# Server_CPU_Sub_Power_Supplies.net
KiCad netlist of a schematic drawn in Altium Designer
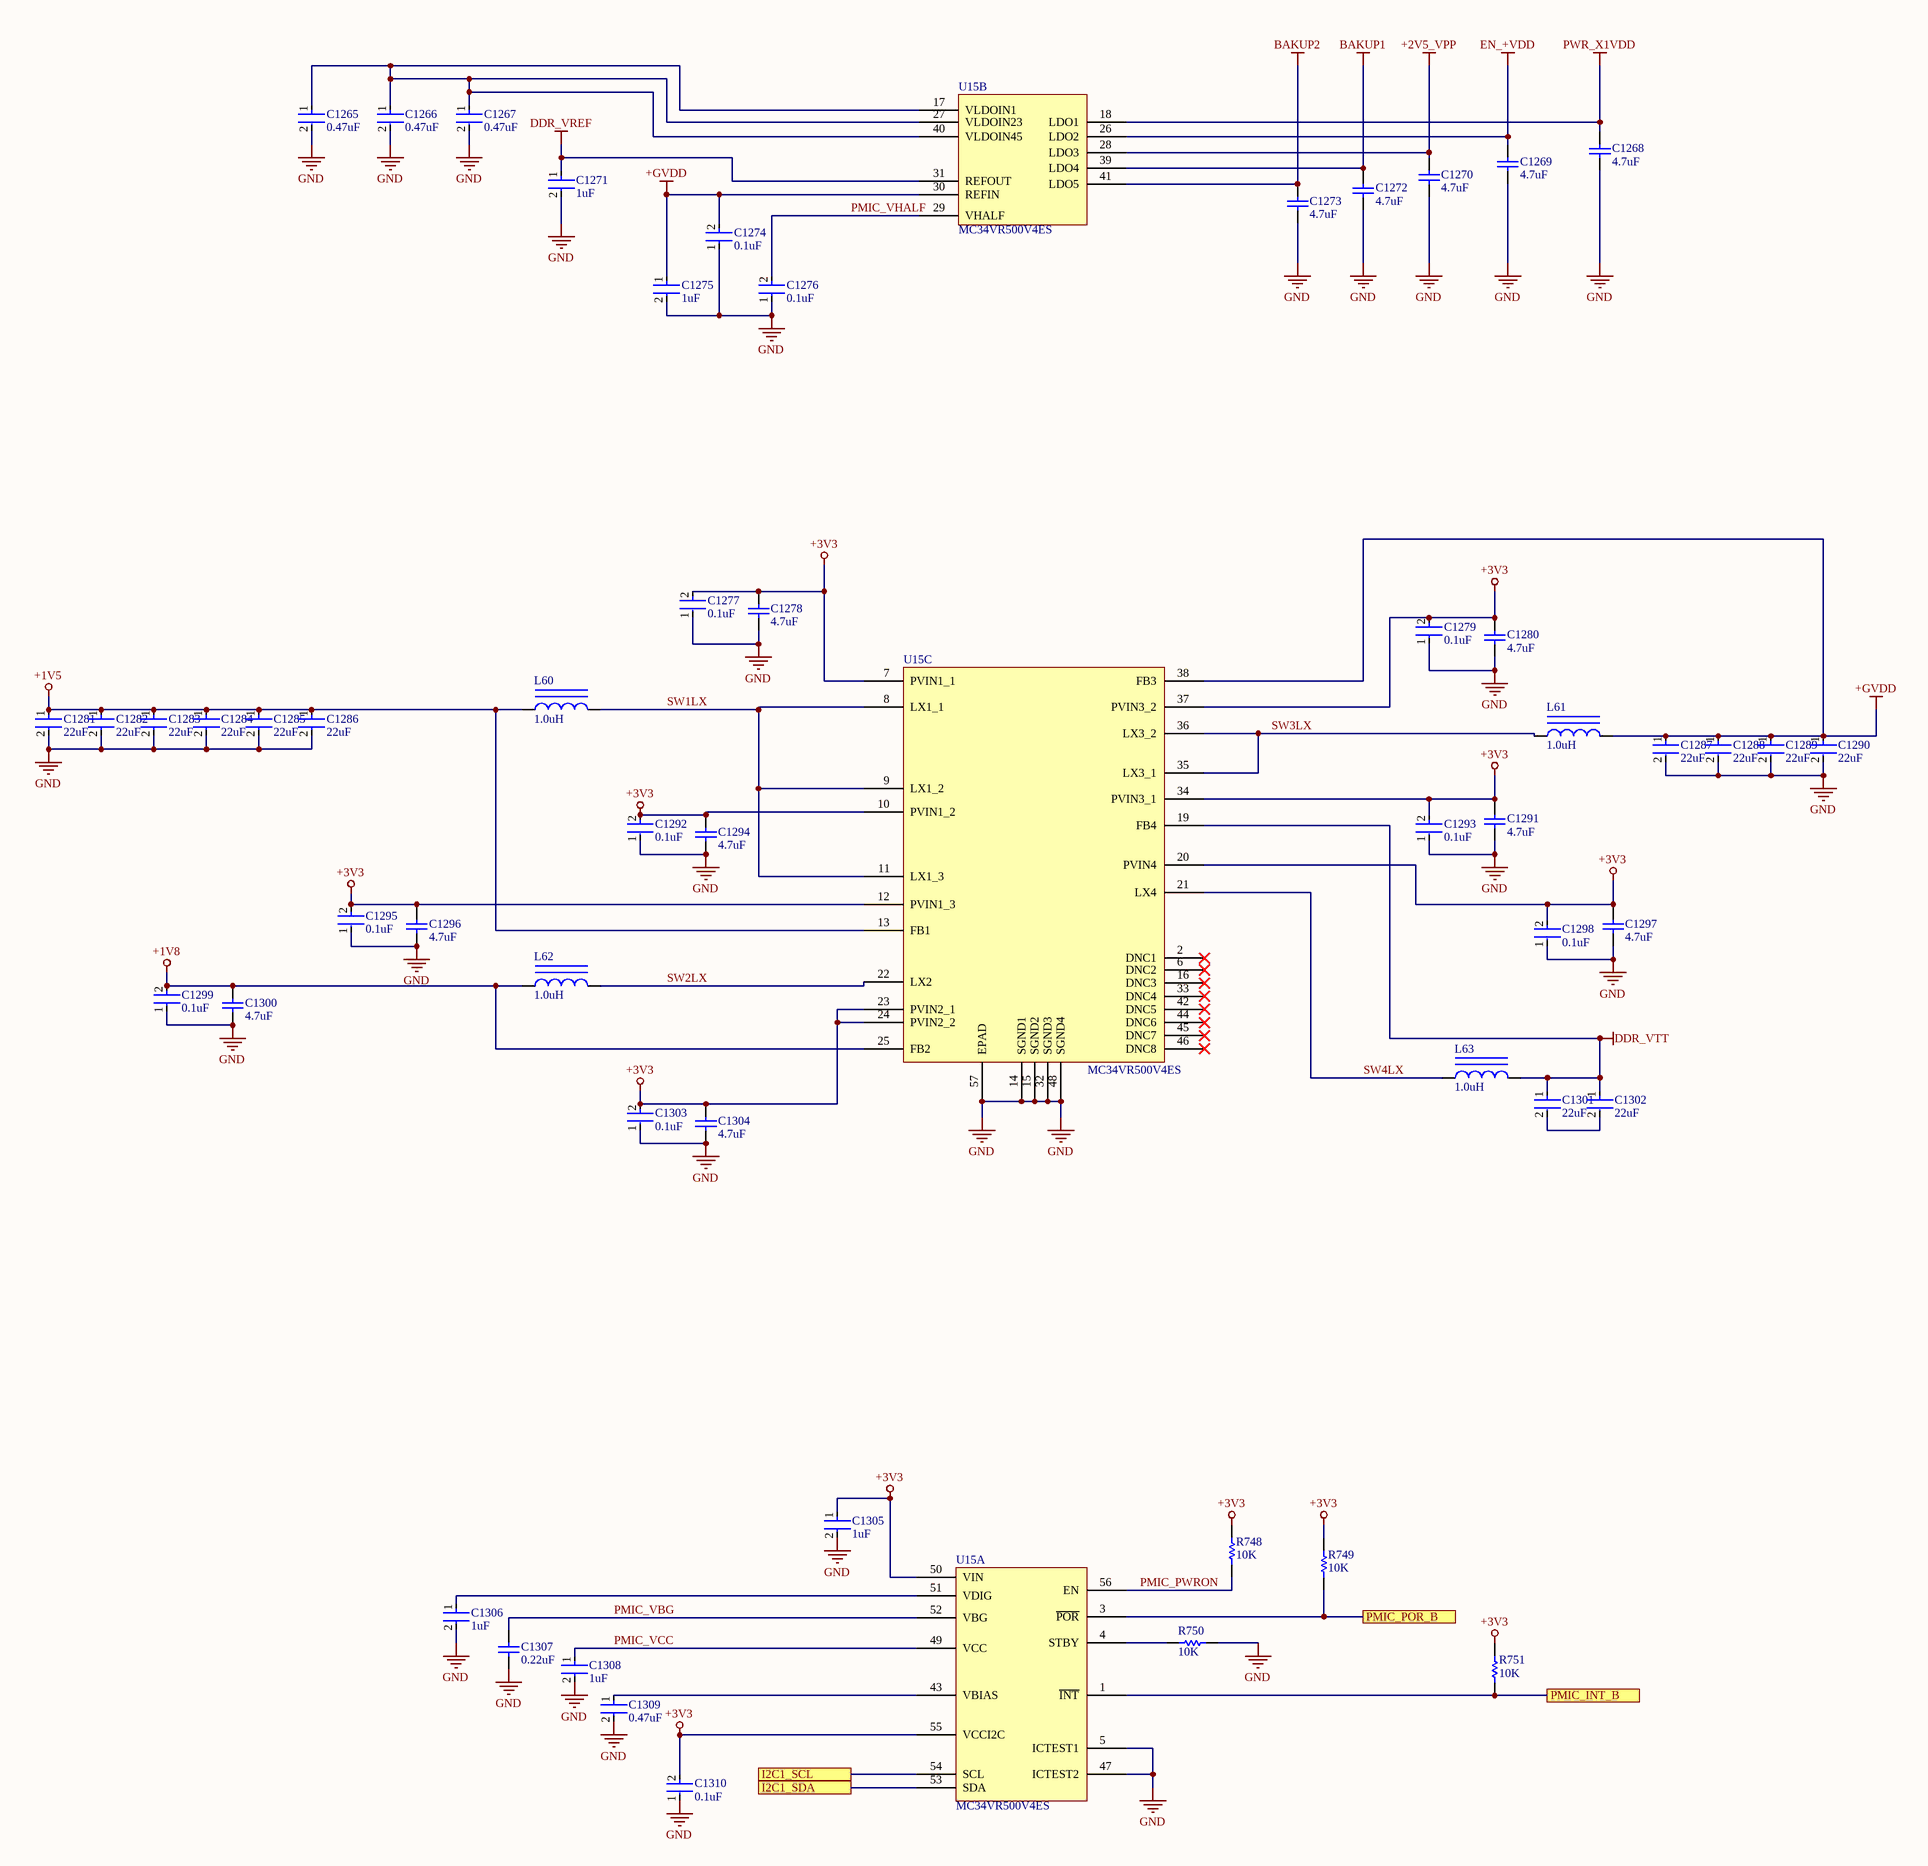
[diagram p0: Server_CPU_Sub_Power_Supplies.SchDoc]

(export (version "E")
  (design (tool "Eeschema 10.0.6"))
  (components
    (comp (ref "C1265")
      (value "0.47uF")
      (footprint "FP-GRM188-0_1-e0_2_0_5-IPC_B")
      (description "Chip Multilayer Ceramic Capacitors for General Purpose, 0603, 0.47uF, X7R, 15%, 10%, 16V")
      (fields (field (name "VOLTAGE") "16V") (field (name "TOLERANCE") "10%"))
      (libsource (lib "Altium Content Vault") (part "11868f565c42a9108669ba33697ecf6"))
    )
    (comp (ref "C1266")
      (value "0.47uF")
      (footprint "FP-GRM188-0_1-e0_2_0_5-IPC_B")
      (description "Chip Multilayer Ceramic Capacitors for General Purpose, 0603, 0.47uF, X7R, 15%, 10%, 16V")
      (fields (field (name "VOLTAGE") "16V") (field (name "TOLERANCE") "10%"))
      (libsource (lib "Altium Content Vault") (part "11868f565c42a9108669ba33697ecf6"))
    )
    (comp (ref "C1267")
      (value "0.47uF")
      (footprint "FP-GRM188-0_1-e0_2_0_5-IPC_B")
      (description "Chip Multilayer Ceramic Capacitors for General Purpose, 0603, 0.47uF, X7R, 15%, 10%, 16V")
      (fields (field (name "VOLTAGE") "16V") (field (name "TOLERANCE") "10%"))
      (libsource (lib "Altium Content Vault") (part "11868f565c42a9108669ba33697ecf6"))
    )
    (comp (ref "C1268")
      (value "4.7uF")
      (footprint "CAPC2013X145X50ML20T25")
      (fields (field (name "MANUFACTURER") "Kemet") (field (name "PART NUMBER") "C0805C475K3PACTU"))
      (libsource (lib "Altium Content Vault") (part "CAP"))
    )
    (comp (ref "C1269")
      (value "4.7uF")
      (footprint "CAPC2013X145X50ML20T25")
      (fields (field (name "MANUFACTURER") "Kemet") (field (name "PART NUMBER") "C0805C475K3PACTU"))
      (libsource (lib "Altium Content Vault") (part "CAP"))
    )
    (comp (ref "C1270")
      (value "4.7uF")
      (footprint "CAPC2013X145X50ML20T25")
      (fields (field (name "MANUFACTURER") "Kemet") (field (name "PART NUMBER") "C0805C475K3PACTU"))
      (libsource (lib "Altium Content Vault") (part "CAP"))
    )
    (comp (ref "C1271")
      (value "1uF")
      (footprint "FP-GRM15-0_1-MFG")
      (description "CAP CER 1UF 10V X5R 0402")
      (fields
        (field (name "OCTOPART") "https://octopart.com/grm155r61a105ke15d-murata-197442")
        (field (name "MANUFACTURER PART NUMBER") "GRM155R61A105KE15D")
      )
      (libsource (lib "Altium Content Vault") (part "02cd4be3c70576c341d710602a673aa"))
    )
    (comp (ref "C1272")
      (value "4.7uF")
      (footprint "CAPC2013X145X50ML20T25")
      (fields (field (name "MANUFACTURER") "Kemet") (field (name "PART NUMBER") "C0805C475K3PACTU"))
      (libsource (lib "Altium Content Vault") (part "CAP"))
    )
    (comp (ref "C1273")
      (value "4.7uF")
      (footprint "CAPC2013X145X50ML20T25")
      (fields (field (name "MANUFACTURER") "Kemet") (field (name "PART NUMBER") "C0805C475K3PACTU"))
      (libsource (lib "Altium Content Vault") (part "CAP"))
    )
    (comp (ref "C1274")
      (value "0.1uF")
      (footprint "FP-GRM15-MFG")
      (description "CAP CER 0.1UF 16V X7R 0402")
      (fields (field (name "MANUFACTURER PART NUMBER") "GRM155R71C104KA88D") (field (name "TOLERANCE") "10%"))
      (libsource (lib "Altium Content Vault") (part "236180d848d6139a670b325ea6854c9"))
    )
    (comp (ref "C1275")
      (value "1uF")
      (footprint "FP-GRM15-0_1-MFG")
      (description "CAP CER 1UF 10V X5R 0402")
      (fields
        (field (name "OCTOPART") "https://octopart.com/grm155r61a105ke15d-murata-197442")
        (field (name "MANUFACTURER PART NUMBER") "GRM155R61A105KE15D")
      )
      (libsource (lib "Altium Content Vault") (part "02cd4be3c70576c341d710602a673aa"))
    )
    (comp (ref "C1276")
      (value "0.1uF")
      (footprint "FP-GRM15-MFG")
      (description "CAP CER 0.1UF 16V X7R 0402")
      (fields (field (name "MANUFACTURER PART NUMBER") "GRM155R71C104KA88D") (field (name "TOLERANCE") "10%"))
      (libsource (lib "Altium Content Vault") (part "236180d848d6139a670b325ea6854c9"))
    )
    (comp (ref "C1277")
      (value "0.1uF")
      (footprint "FP-GRM15-MFG")
      (description "CAP CER 0.1UF 16V X7R 0402")
      (fields (field (name "MANUFACTURER PART NUMBER") "GRM155R71C104KA88D") (field (name "TOLERANCE") "10%"))
      (libsource (lib "Altium Content Vault") (part "236180d848d6139a670b325ea6854c9"))
    )
    (comp (ref "C1278")
      (value "4.7uF")
      (footprint "CAPC2013X145X50ML20T25")
      (fields (field (name "MANUFACTURER") "Kemet") (field (name "PART NUMBER") "C0805C475K3PACTU"))
      (libsource (lib "Altium Content Vault") (part "CAP"))
    )
    (comp (ref "C1279")
      (value "0.1uF")
      (footprint "FP-GRM15-MFG")
      (description "CAP CER 0.1UF 16V X7R 0402")
      (fields (field (name "MANUFACTURER PART NUMBER") "GRM155R71C104KA88D") (field (name "TOLERANCE") "10%"))
      (libsource (lib "Altium Content Vault") (part "236180d848d6139a670b325ea6854c9"))
    )
    (comp (ref "C1280")
      (value "4.7uF")
      (footprint "CAPC2013X145X50ML20T25")
      (fields (field (name "MANUFACTURER") "Kemet") (field (name "PART NUMBER") "C0805C475K3PACTU"))
      (libsource (lib "Altium Content Vault") (part "CAP"))
    )
    (comp (ref "C1281")
      (value "22uF")
      (footprint "FP-GRM21B-0_15-MFG")
      (description "Chip Multilayer Ceramic Capacitors for General Purpose, 0805, 22uF, X5R, 15%, 20%, 6.3V")
      (fields (field (name "VOLTAGE") "6.3V") (field (name "TOLERANCE") "20%"))
      (libsource (lib "Altium Content Vault") (part "b4654b650e69147ec39a6b967a45e02"))
    )
    (comp (ref "C1282")
      (value "22uF")
      (footprint "FP-GRM21B-0_15-MFG")
      (description "Chip Multilayer Ceramic Capacitors for General Purpose, 0805, 22uF, X5R, 15%, 20%, 6.3V")
      (fields (field (name "VOLTAGE") "6.3V") (field (name "TOLERANCE") "20%"))
      (libsource (lib "Altium Content Vault") (part "b4654b650e69147ec39a6b967a45e02"))
    )
    (comp (ref "C1283")
      (value "22uF")
      (footprint "FP-GRM21B-0_15-MFG")
      (description "Chip Multilayer Ceramic Capacitors for General Purpose, 0805, 22uF, X5R, 15%, 20%, 6.3V")
      (fields (field (name "VOLTAGE") "6.3V") (field (name "TOLERANCE") "20%"))
      (libsource (lib "Altium Content Vault") (part "b4654b650e69147ec39a6b967a45e02"))
    )
    (comp (ref "C1284")
      (value "22uF")
      (footprint "FP-GRM21B-0_15-MFG")
      (description "Chip Multilayer Ceramic Capacitors for General Purpose, 0805, 22uF, X5R, 15%, 20%, 6.3V")
      (fields (field (name "VOLTAGE") "6.3V") (field (name "TOLERANCE") "20%"))
      (libsource (lib "Altium Content Vault") (part "b4654b650e69147ec39a6b967a45e02"))
    )
    (comp (ref "C1285")
      (value "22uF")
      (footprint "FP-GRM21B-0_15-MFG")
      (description "Chip Multilayer Ceramic Capacitors for General Purpose, 0805, 22uF, X5R, 15%, 20%, 6.3V")
      (fields (field (name "VOLTAGE") "6.3V") (field (name "TOLERANCE") "20%"))
      (libsource (lib "Altium Content Vault") (part "b4654b650e69147ec39a6b967a45e02"))
    )
    (comp (ref "C1286")
      (value "22uF")
      (footprint "FP-GRM21B-0_15-MFG")
      (description "Chip Multilayer Ceramic Capacitors for General Purpose, 0805, 22uF, X5R, 15%, 20%, 6.3V")
      (fields (field (name "VOLTAGE") "6.3V") (field (name "TOLERANCE") "20%"))
      (libsource (lib "Altium Content Vault") (part "b4654b650e69147ec39a6b967a45e02"))
    )
    (comp (ref "C1287")
      (value "22uF")
      (footprint "FP-GRM21B-0_15-MFG")
      (description "Chip Multilayer Ceramic Capacitors for General Purpose, 0805, 22uF, X5R, 15%, 20%, 6.3V")
      (fields (field (name "VOLTAGE") "6.3V") (field (name "TOLERANCE") "20%"))
      (libsource (lib "Altium Content Vault") (part "b4654b650e69147ec39a6b967a45e02"))
    )
    (comp (ref "C1288")
      (value "22uF")
      (footprint "FP-GRM21B-0_15-MFG")
      (description "Chip Multilayer Ceramic Capacitors for General Purpose, 0805, 22uF, X5R, 15%, 20%, 6.3V")
      (fields (field (name "VOLTAGE") "6.3V") (field (name "TOLERANCE") "20%"))
      (libsource (lib "Altium Content Vault") (part "b4654b650e69147ec39a6b967a45e02"))
    )
    (comp (ref "C1289")
      (value "22uF")
      (footprint "FP-GRM21B-0_15-MFG")
      (description "Chip Multilayer Ceramic Capacitors for General Purpose, 0805, 22uF, X5R, 15%, 20%, 6.3V")
      (fields (field (name "VOLTAGE") "6.3V") (field (name "TOLERANCE") "20%"))
      (libsource (lib "Altium Content Vault") (part "b4654b650e69147ec39a6b967a45e02"))
    )
    (comp (ref "C1290")
      (value "22uF")
      (footprint "FP-GRM21B-0_15-MFG")
      (description "Chip Multilayer Ceramic Capacitors for General Purpose, 0805, 22uF, X5R, 15%, 20%, 6.3V")
      (fields (field (name "VOLTAGE") "6.3V") (field (name "TOLERANCE") "20%"))
      (libsource (lib "Altium Content Vault") (part "b4654b650e69147ec39a6b967a45e02"))
    )
    (comp (ref "C1291")
      (value "4.7uF")
      (footprint "CAPC2013X145X50ML20T25")
      (fields (field (name "MANUFACTURER") "Kemet") (field (name "PART NUMBER") "C0805C475K3PACTU"))
      (libsource (lib "Altium Content Vault") (part "CAP"))
    )
    (comp (ref "C1292")
      (value "0.1uF")
      (footprint "FP-GRM15-MFG")
      (description "CAP CER 0.1UF 16V X7R 0402")
      (fields (field (name "MANUFACTURER PART NUMBER") "GRM155R71C104KA88D") (field (name "TOLERANCE") "10%"))
      (libsource (lib "Altium Content Vault") (part "236180d848d6139a670b325ea6854c9"))
    )
    (comp (ref "C1293")
      (value "0.1uF")
      (footprint "FP-GRM15-MFG")
      (description "CAP CER 0.1UF 16V X7R 0402")
      (fields (field (name "MANUFACTURER PART NUMBER") "GRM155R71C104KA88D") (field (name "TOLERANCE") "10%"))
      (libsource (lib "Altium Content Vault") (part "236180d848d6139a670b325ea6854c9"))
    )
    (comp (ref "C1294")
      (value "4.7uF")
      (footprint "CAPC2013X145X50ML20T25")
      (fields (field (name "MANUFACTURER") "Kemet") (field (name "PART NUMBER") "C0805C475K3PACTU"))
      (libsource (lib "Altium Content Vault") (part "CAP"))
    )
    (comp (ref "C1295")
      (value "0.1uF")
      (footprint "FP-GRM15-MFG")
      (description "CAP CER 0.1UF 16V X7R 0402")
      (fields (field (name "MANUFACTURER PART NUMBER") "GRM155R71C104KA88D") (field (name "TOLERANCE") "10%"))
      (libsource (lib "Altium Content Vault") (part "236180d848d6139a670b325ea6854c9"))
    )
    (comp (ref "C1296")
      (value "4.7uF")
      (footprint "CAPC2013X145X50ML20T25")
      (fields (field (name "MANUFACTURER") "Kemet") (field (name "PART NUMBER") "C0805C475K3PACTU"))
      (libsource (lib "Altium Content Vault") (part "CAP"))
    )
    (comp (ref "C1297")
      (value "4.7uF")
      (footprint "CAPC2013X145X50ML20T25")
      (fields (field (name "MANUFACTURER") "Kemet") (field (name "PART NUMBER") "C0805C475K3PACTU"))
      (libsource (lib "Altium Content Vault") (part "CAP"))
    )
    (comp (ref "C1298")
      (value "0.1uF")
      (footprint "FP-GRM15-MFG")
      (description "CAP CER 0.1UF 16V X7R 0402")
      (fields (field (name "MANUFACTURER PART NUMBER") "GRM155R71C104KA88D") (field (name "TOLERANCE") "10%"))
      (libsource (lib "Altium Content Vault") (part "236180d848d6139a670b325ea6854c9"))
    )
    (comp (ref "C1299")
      (value "0.1uF")
      (footprint "FP-GRM15-MFG")
      (description "CAP CER 0.1UF 16V X7R 0402")
      (fields (field (name "MANUFACTURER PART NUMBER") "GRM155R71C104KA88D") (field (name "TOLERANCE") "10%"))
      (libsource (lib "Altium Content Vault") (part "236180d848d6139a670b325ea6854c9"))
    )
    (comp (ref "C1300")
      (value "4.7uF")
      (footprint "CAPC2013X145X50ML20T25")
      (fields (field (name "MANUFACTURER") "Kemet") (field (name "PART NUMBER") "C0805C475K3PACTU"))
      (libsource (lib "Altium Content Vault") (part "CAP"))
    )
    (comp (ref "C1301")
      (value "22uF")
      (footprint "FP-GRM21B-0_15-MFG")
      (description "Chip Multilayer Ceramic Capacitors for General Purpose, 0805, 22uF, X5R, 15%, 20%, 6.3V")
      (fields (field (name "VOLTAGE") "6.3V") (field (name "TOLERANCE") "20%"))
      (libsource (lib "Altium Content Vault") (part "b4654b650e69147ec39a6b967a45e02"))
    )
    (comp (ref "C1302")
      (value "22uF")
      (footprint "FP-GRM21B-0_15-MFG")
      (description "Chip Multilayer Ceramic Capacitors for General Purpose, 0805, 22uF, X5R, 15%, 20%, 6.3V")
      (fields (field (name "VOLTAGE") "6.3V") (field (name "TOLERANCE") "20%"))
      (libsource (lib "Altium Content Vault") (part "b4654b650e69147ec39a6b967a45e02"))
    )
    (comp (ref "C1303")
      (value "0.1uF")
      (footprint "FP-GRM15-MFG")
      (description "CAP CER 0.1UF 16V X7R 0402")
      (fields (field (name "MANUFACTURER PART NUMBER") "GRM155R71C104KA88D") (field (name "TOLERANCE") "10%"))
      (libsource (lib "Altium Content Vault") (part "236180d848d6139a670b325ea6854c9"))
    )
    (comp (ref "C1304")
      (value "4.7uF")
      (footprint "CAPC2013X145X50ML20T25")
      (fields (field (name "MANUFACTURER") "Kemet") (field (name "PART NUMBER") "C0805C475K3PACTU"))
      (libsource (lib "Altium Content Vault") (part "CAP"))
    )
    (comp (ref "C1305")
      (value "1uF")
      (footprint "FP-GRM15-0_1-MFG")
      (description "CAP CER 1UF 10V X5R 0402")
      (fields
        (field (name "OCTOPART") "https://octopart.com/grm155r61a105ke15d-murata-197442")
        (field (name "MANUFACTURER PART NUMBER") "GRM155R61A105KE15D")
      )
      (libsource (lib "Altium Content Vault") (part "02cd4be3c70576c341d710602a673aa"))
    )
    (comp (ref "C1306")
      (value "1uF")
      (footprint "FP-GRM15-0_1-MFG")
      (description "CAP CER 1UF 10V X5R 0402")
      (fields
        (field (name "OCTOPART") "https://octopart.com/grm155r61a105ke15d-murata-197442")
        (field (name "MANUFACTURER PART NUMBER") "GRM155R61A105KE15D")
      )
      (libsource (lib "Altium Content Vault") (part "02cd4be3c70576c341d710602a673aa"))
    )
    (comp (ref "C1307")
      (value "0.22uF")
      (footprint "CAPC1005X55X25NL05T10")
      (description "Chip Capacitor, 220 nF, +/- 10%, 10 V, -55 to 85 degC, 0402 (1005 Metric), RoHS, Tape and Reel")
      (fields (field (name "MANUFACTURER") "Basic Passives") (field (name "TOLERANCE") "10%"))
      (libsource (lib "Altium Content Vault") (part "CAP-NP-2"))
    )
    (comp (ref "C1308")
      (value "1uF")
      (footprint "FP-GRM15-0_1-MFG")
      (description "CAP CER 1UF 10V X5R 0402")
      (fields
        (field (name "OCTOPART") "https://octopart.com/grm155r61a105ke15d-murata-197442")
        (field (name "MANUFACTURER PART NUMBER") "GRM155R61A105KE15D")
      )
      (libsource (lib "Altium Content Vault") (part "02cd4be3c70576c341d710602a673aa"))
    )
    (comp (ref "C1309")
      (value "0.47uF")
      (footprint "FP-GRM188-0_1-e0_2_0_5-IPC_B")
      (description "Chip Multilayer Ceramic Capacitors for General Purpose, 0603, 0.47uF, X7R, 15%, 10%, 16V")
      (fields (field (name "VOLTAGE") "16V") (field (name "TOLERANCE") "10%"))
      (libsource (lib "Altium Content Vault") (part "11868f565c42a9108669ba33697ecf6"))
    )
    (comp (ref "C1310")
      (value "0.1uF")
      (footprint "FP-GRM15-MFG")
      (description "CAP CER 0.1UF 16V X7R 0402")
      (fields (field (name "MANUFACTURER PART NUMBER") "GRM155R71C104KA88D") (field (name "TOLERANCE") "10%"))
      (libsource (lib "Altium Content Vault") (part "236180d848d6139a670b325ea6854c9"))
    )
    (comp (ref "L60")
      (value "1.0uH")
      (footprint "BOUR-CM45_L")
      (description "Chip Inductor, 1 uH, +/- 10%, 450 mA, -40 to 125 degC, 2-Pin SMD (1812), RoHS, Tape and Reel")
      (fields (field (name "MANUFACTURER") "Bourns"))
      (libsource (lib "Altium Content Vault") (part "IND-IRON-2"))
    )
    (comp (ref "L61")
      (value "1.0uH")
      (footprint "BOUR-CM45_L")
      (description "Chip Inductor, 1 uH, +/- 10%, 450 mA, -40 to 125 degC, 2-Pin SMD (1812), RoHS, Tape and Reel")
      (fields (field (name "MANUFACTURER") "Bourns"))
      (libsource (lib "Altium Content Vault") (part "IND-IRON-2"))
    )
    (comp (ref "L62")
      (value "1.0uH")
      (footprint "BOUR-CM45_L")
      (description "Chip Inductor, 1 uH, +/- 10%, 450 mA, -40 to 125 degC, 2-Pin SMD (1812), RoHS, Tape and Reel")
      (fields (field (name "MANUFACTURER") "Bourns"))
      (libsource (lib "Altium Content Vault") (part "IND-IRON-2"))
    )
    (comp (ref "L63")
      (value "1.0uH")
      (footprint "BOUR-CM45_L")
      (description "Chip Inductor, 1 uH, +/- 10%, 450 mA, -40 to 125 degC, 2-Pin SMD (1812), RoHS, Tape and Reel")
      (fields (field (name "MANUFACTURER") "Bourns"))
      (libsource (lib "Altium Content Vault") (part "IND-IRON-2"))
    )
    (comp (ref "R748")
      (value "10K")
      (footprint "RESC1005X40X25LL05T05")
      (description "Chip Resistor, 10 KOhm, +/- 1%, 0.1 W, -55 to 155 degC, 0402 (1005 Metric), RoHS, Tape and Reel")
      (fields (field (name "TOLERANCE") "1%") (field (name "MANUFACTURER") "Panasonic"))
      (libsource (lib "Altium Content Vault") (part "RES-2"))
    )
    (comp (ref "R749")
      (value "10K")
      (footprint "RESC1005X40X25LL05T05")
      (description "Chip Resistor, 10 KOhm, +/- 1%, 0.1 W, -55 to 155 degC, 0402 (1005 Metric), RoHS, Tape and Reel")
      (fields (field (name "TOLERANCE") "1%") (field (name "MANUFACTURER") "Panasonic"))
      (libsource (lib "Altium Content Vault") (part "RES-2"))
    )
    (comp (ref "R750")
      (value "10K")
      (footprint "RESC1005X40X25LL05T05")
      (description "Chip Resistor, 10 KOhm, +/- 1%, 0.1 W, -55 to 155 degC, 0402 (1005 Metric), RoHS, Tape and Reel")
      (fields (field (name "TOLERANCE") "1%") (field (name "MANUFACTURER") "Panasonic"))
      (libsource (lib "Altium Content Vault") (part "RES-2"))
    )
    (comp (ref "R751")
      (value "10K")
      (footprint "RESC1005X40X25LL05T05")
      (description "Chip Resistor, 10 KOhm, +/- 1%, 0.1 W, -55 to 155 degC, 0402 (1005 Metric), RoHS, Tape and Reel")
      (fields (field (name "TOLERANCE") "1%") (field (name "MANUFACTURER") "Panasonic"))
      (libsource (lib "Altium Content Vault") (part "RES-2"))
    )
    (comp (ref "U15")
      (value "MC34VR500V4ES")
      (footprint "MC34VR500V4ES:QFN50P800X800X90-57N")
      (description "Regulator, Buck, Quad with up to 4.5A Output and Triple User-programmable LDOs, QFN 56, Tray")
      (fields (field (name "MF") "{'manufacturer': u'NXP Semiconductors'}"))
      (libsource (lib "MC34VR500V4ES") (part "MC34VR500V4ES"))
    )
  )
  (nets
    (net (code "1") (name "+1V5") (class "Default")
      (node (ref "C1281") (pin "1") (pinfunction "1_1") (pintype "passive"))
      (node (ref "C1282") (pin "1") (pinfunction "1_1") (pintype "passive"))
      (node (ref "C1283") (pin "1") (pinfunction "1_1") (pintype "passive"))
      (node (ref "C1284") (pin "1") (pinfunction "1_1") (pintype "passive"))
      (node (ref "C1285") (pin "1") (pinfunction "1_1") (pintype "passive"))
      (node (ref "C1286") (pin "1") (pinfunction "1_1") (pintype "passive"))
      (node (ref "L60") (pin "1") (pinfunction "1_1") (pintype "passive"))
      (node (ref "U15") (pin "13") (pinfunction "FB1_13") (pintype "passive"))
    )
    (net (code "2") (name "+1V8") (class "Default")
      (node (ref "C1299") (pin "2") (pinfunction "2_2") (pintype "passive"))
      (node (ref "C1300") (pin "2") (pinfunction "2_2") (pintype "passive"))
      (node (ref "L62") (pin "1") (pinfunction "1_1") (pintype "passive"))
      (node (ref "U15") (pin "25") (pinfunction "FB2_25") (pintype "passive"))
    )
    (net (code "3") (name "+2V5_VPP") (class "Default")
      (node (ref "C1270") (pin "2") (pinfunction "2_2") (pintype "passive"))
      (node (ref "U15") (pin "28") (pinfunction "LDO3_28") (pintype "passive"))
    )
    (net (code "4") (name "+3V3") (class "Default")
      (node (ref "C1277") (pin "2") (pinfunction "2_2") (pintype "passive"))
      (node (ref "C1278") (pin "2") (pinfunction "2_2") (pintype "passive"))
      (node (ref "C1279") (pin "2") (pinfunction "2_2") (pintype "passive"))
      (node (ref "C1280") (pin "2") (pinfunction "2_2") (pintype "passive"))
      (node (ref "C1291") (pin "2") (pinfunction "2_2") (pintype "passive"))
      (node (ref "C1292") (pin "2") (pinfunction "2_2") (pintype "passive"))
      (node (ref "C1293") (pin "2") (pinfunction "2_2") (pintype "passive"))
      (node (ref "C1294") (pin "2") (pinfunction "2_2") (pintype "passive"))
      (node (ref "C1295") (pin "2") (pinfunction "2_2") (pintype "passive"))
      (node (ref "C1296") (pin "2") (pinfunction "2_2") (pintype "passive"))
      (node (ref "C1297") (pin "2") (pinfunction "2_2") (pintype "passive"))
      (node (ref "C1298") (pin "2") (pinfunction "2_2") (pintype "passive"))
      (node (ref "C1303") (pin "2") (pinfunction "2_2") (pintype "passive"))
      (node (ref "C1304") (pin "2") (pinfunction "2_2") (pintype "passive"))
      (node (ref "C1305") (pin "1") (pinfunction "1_1") (pintype "passive"))
      (node (ref "C1310") (pin "2") (pinfunction "2_2") (pintype "passive"))
      (node (ref "R748") (pin "2") (pinfunction "2_2") (pintype "passive"))
      (node (ref "R749") (pin "2") (pinfunction "2_2") (pintype "passive"))
      (node (ref "R751") (pin "2") (pinfunction "2_2") (pintype "passive"))
      (node (ref "U15") (pin "10") (pinfunction "PVIN1_2_10") (pintype "passive"))
      (node (ref "U15") (pin "12") (pinfunction "PVIN1_3_12") (pintype "passive"))
      (node (ref "U15") (pin "20") (pinfunction "PVIN4_20") (pintype "passive"))
      (node (ref "U15") (pin "23") (pinfunction "PVIN2_1_23") (pintype "passive"))
      (node (ref "U15") (pin "24") (pinfunction "PVIN2_2_24") (pintype "passive"))
      (node (ref "U15") (pin "34") (pinfunction "PVIN3_1_34") (pintype "passive"))
      (node (ref "U15") (pin "37") (pinfunction "PVIN3_2_37") (pintype "passive"))
      (node (ref "U15") (pin "50") (pinfunction "VIN_50") (pintype "passive"))
      (node (ref "U15") (pin "55") (pinfunction "VCCI2C_55") (pintype "passive"))
      (node (ref "U15") (pin "7") (pinfunction "PVIN1_1_7") (pintype "passive"))
    )
    (net (code "5") (name "+GVDD") (class "Default")
      (node (ref "C1274") (pin "2") (pinfunction "2_2") (pintype "passive"))
      (node (ref "C1275") (pin "1") (pinfunction "1_1") (pintype "passive"))
      (node (ref "C1287") (pin "1") (pinfunction "1_1") (pintype "passive"))
      (node (ref "C1288") (pin "1") (pinfunction "1_1") (pintype "passive"))
      (node (ref "C1289") (pin "1") (pinfunction "1_1") (pintype "passive"))
      (node (ref "C1290") (pin "1") (pinfunction "1_1") (pintype "passive"))
      (node (ref "L61") (pin "2") (pinfunction "2_2") (pintype "passive"))
      (node (ref "U15") (pin "30") (pinfunction "REFIN_30") (pintype "passive"))
      (node (ref "U15") (pin "38") (pinfunction "FB3_38") (pintype "passive"))
    )
    (net (code "6") (name "/I2C1_SCL") (class "Default")
      (node (ref "U15") (pin "54") (pinfunction "SCL_54") (pintype "passive"))
    )
    (net (code "7") (name "/I2C1_SDA") (class "Default")
      (node (ref "U15") (pin "53") (pinfunction "SDA_53") (pintype "passive"))
    )
    (net (code "8") (name "/PMIC_INT_B") (class "Default")
      (node (ref "R751") (pin "1") (pinfunction "1_1") (pintype "passive"))
      (node (ref "U15") (pin "1") (pinfunction "~{INT}_1") (pintype "passive"))
    )
    (net (code "9") (name "/PMIC_POR_B") (class "Default")
      (node (ref "R749") (pin "1") (pinfunction "1_1") (pintype "passive"))
      (node (ref "U15") (pin "3") (pinfunction "~{POR}_3") (pintype "passive"))
    )
    (net (code "10") (name "/PMIC_PWRON") (class "Default")
      (node (ref "R748") (pin "1") (pinfunction "1_1") (pintype "passive"))
      (node (ref "U15") (pin "56") (pinfunction "EN_56") (pintype "passive"))
    )
    (net (code "11") (name "/PMIC_VBG") (class "Default")
      (node (ref "C1307") (pin "2") (pinfunction "2_2") (pintype "passive"))
      (node (ref "U15") (pin "52") (pinfunction "VBG_52") (pintype "passive"))
    )
    (net (code "12") (name "/PMIC_VCC") (class "Default")
      (node (ref "C1308") (pin "1") (pinfunction "1_1") (pintype "passive"))
      (node (ref "U15") (pin "49") (pinfunction "VCC_49") (pintype "passive"))
    )
    (net (code "13") (name "/PMIC_VHALF") (class "Default")
      (node (ref "C1276") (pin "2") (pinfunction "2_2") (pintype "passive"))
      (node (ref "U15") (pin "29") (pinfunction "VHALF_29") (pintype "passive"))
    )
    (net (code "14") (name "/SW1LX") (class "Default")
      (node (ref "L60") (pin "2") (pinfunction "2_2") (pintype "passive"))
      (node (ref "U15") (pin "11") (pinfunction "LX1_3_11") (pintype "passive"))
      (node (ref "U15") (pin "8") (pinfunction "LX1_1_8") (pintype "passive"))
      (node (ref "U15") (pin "9") (pinfunction "LX1_2_9") (pintype "passive"))
    )
    (net (code "15") (name "/SW2LX") (class "Default")
      (node (ref "L62") (pin "2") (pinfunction "2_2") (pintype "passive"))
      (node (ref "U15") (pin "22") (pinfunction "LX2_22") (pintype "passive"))
    )
    (net (code "16") (name "/SW3LX") (class "Default")
      (node (ref "L61") (pin "1") (pinfunction "1_1") (pintype "passive"))
      (node (ref "U15") (pin "35") (pinfunction "LX3_1_35") (pintype "passive"))
      (node (ref "U15") (pin "36") (pinfunction "LX3_2_36") (pintype "passive"))
    )
    (net (code "17") (name "/SW4LX") (class "Default")
      (node (ref "L63") (pin "1") (pinfunction "1_1") (pintype "passive"))
      (node (ref "U15") (pin "21") (pinfunction "LX4_21") (pintype "passive"))
    )
    (net (code "18") (name "BAKUP1") (class "Default")
      (node (ref "C1272") (pin "2") (pinfunction "2_2") (pintype "passive"))
      (node (ref "U15") (pin "39") (pinfunction "LDO4_39") (pintype "passive"))
    )
    (net (code "19") (name "BAKUP2") (class "Default")
      (node (ref "C1273") (pin "2") (pinfunction "2_2") (pintype "passive"))
      (node (ref "U15") (pin "41") (pinfunction "LDO5_41") (pintype "passive"))
    )
    (net (code "20") (name "DDR_VREF") (class "Default")
      (node (ref "C1271") (pin "1") (pinfunction "1_1") (pintype "passive"))
      (node (ref "U15") (pin "31") (pinfunction "REFOUT_31") (pintype "passive"))
    )
    (net (code "21") (name "DDR_VTT") (class "Default")
      (node (ref "C1301") (pin "1") (pinfunction "1_1") (pintype "passive"))
      (node (ref "C1302") (pin "1") (pinfunction "1_1") (pintype "passive"))
      (node (ref "L63") (pin "2") (pinfunction "2_2") (pintype "passive"))
      (node (ref "U15") (pin "19") (pinfunction "FB4_19") (pintype "passive"))
    )
    (net (code "22") (name "EN_+VDD") (class "Default")
      (node (ref "C1269") (pin "2") (pinfunction "2_2") (pintype "passive"))
      (node (ref "U15") (pin "26") (pinfunction "LDO2_26") (pintype "passive"))
    )
    (net (code "23") (name "GND") (class "Default")
      (node (ref "C1265") (pin "2") (pinfunction "2_2") (pintype "passive"))
      (node (ref "C1266") (pin "2") (pinfunction "2_2") (pintype "passive"))
      (node (ref "C1267") (pin "2") (pinfunction "2_2") (pintype "passive"))
      (node (ref "C1268") (pin "1") (pinfunction "1_1") (pintype "passive"))
      (node (ref "C1269") (pin "1") (pinfunction "1_1") (pintype "passive"))
      (node (ref "C1270") (pin "1") (pinfunction "1_1") (pintype "passive"))
      (node (ref "C1271") (pin "2") (pinfunction "2_2") (pintype "passive"))
      (node (ref "C1272") (pin "1") (pinfunction "1_1") (pintype "passive"))
      (node (ref "C1273") (pin "1") (pinfunction "1_1") (pintype "passive"))
      (node (ref "C1274") (pin "1") (pinfunction "1_1") (pintype "passive"))
      (node (ref "C1275") (pin "2") (pinfunction "2_2") (pintype "passive"))
      (node (ref "C1276") (pin "1") (pinfunction "1_1") (pintype "passive"))
      (node (ref "C1277") (pin "1") (pinfunction "1_1") (pintype "passive"))
      (node (ref "C1278") (pin "1") (pinfunction "1_1") (pintype "passive"))
      (node (ref "C1279") (pin "1") (pinfunction "1_1") (pintype "passive"))
      (node (ref "C1280") (pin "1") (pinfunction "1_1") (pintype "passive"))
      (node (ref "C1281") (pin "2") (pinfunction "2_2") (pintype "passive"))
      (node (ref "C1282") (pin "2") (pinfunction "2_2") (pintype "passive"))
      (node (ref "C1283") (pin "2") (pinfunction "2_2") (pintype "passive"))
      (node (ref "C1284") (pin "2") (pinfunction "2_2") (pintype "passive"))
      (node (ref "C1285") (pin "2") (pinfunction "2_2") (pintype "passive"))
      (node (ref "C1286") (pin "2") (pinfunction "2_2") (pintype "passive"))
      (node (ref "C1287") (pin "2") (pinfunction "2_2") (pintype "passive"))
      (node (ref "C1288") (pin "2") (pinfunction "2_2") (pintype "passive"))
      (node (ref "C1289") (pin "2") (pinfunction "2_2") (pintype "passive"))
      (node (ref "C1290") (pin "2") (pinfunction "2_2") (pintype "passive"))
      (node (ref "C1291") (pin "1") (pinfunction "1_1") (pintype "passive"))
      (node (ref "C1292") (pin "1") (pinfunction "1_1") (pintype "passive"))
      (node (ref "C1293") (pin "1") (pinfunction "1_1") (pintype "passive"))
      (node (ref "C1294") (pin "1") (pinfunction "1_1") (pintype "passive"))
      (node (ref "C1295") (pin "1") (pinfunction "1_1") (pintype "passive"))
      (node (ref "C1296") (pin "1") (pinfunction "1_1") (pintype "passive"))
      (node (ref "C1297") (pin "1") (pinfunction "1_1") (pintype "passive"))
      (node (ref "C1298") (pin "1") (pinfunction "1_1") (pintype "passive"))
      (node (ref "C1299") (pin "1") (pinfunction "1_1") (pintype "passive"))
      (node (ref "C1300") (pin "1") (pinfunction "1_1") (pintype "passive"))
      (node (ref "C1303") (pin "1") (pinfunction "1_1") (pintype "passive"))
      (node (ref "C1304") (pin "1") (pinfunction "1_1") (pintype "passive"))
      (node (ref "C1305") (pin "2") (pinfunction "2_2") (pintype "passive"))
      (node (ref "C1306") (pin "2") (pinfunction "2_2") (pintype "passive"))
      (node (ref "C1307") (pin "1") (pinfunction "1_1") (pintype "passive"))
      (node (ref "C1308") (pin "2") (pinfunction "2_2") (pintype "passive"))
      (node (ref "C1309") (pin "2") (pinfunction "2_2") (pintype "passive"))
      (node (ref "C1310") (pin "1") (pinfunction "1_1") (pintype "passive"))
      (node (ref "R750") (pin "1") (pinfunction "1_1") (pintype "passive"))
      (node (ref "U15") (pin "14") (pinfunction "SGND1_14") (pintype "passive"))
      (node (ref "U15") (pin "15") (pinfunction "SGND2_15") (pintype "passive"))
      (node (ref "U15") (pin "32") (pinfunction "SGND3_32") (pintype "passive"))
      (node (ref "U15") (pin "47") (pinfunction "ICTEST2_47") (pintype "passive"))
      (node (ref "U15") (pin "48") (pinfunction "SGND4_48") (pintype "passive"))
      (node (ref "U15") (pin "5") (pinfunction "ICTEST1_5") (pintype "passive"))
      (node (ref "U15") (pin "57") (pinfunction "EPAD_57") (pintype "passive"))
    )
    (net (code "24") (name "Net-(C1301-Pad2)") (class "Default")
      (node (ref "C1301") (pin "2") (pinfunction "2_2") (pintype "passive"))
      (node (ref "C1302") (pin "2") (pinfunction "2_2") (pintype "passive"))
    )
    (net (code "25") (name "Net-(U15A-STBY)") (class "Default")
      (node (ref "R750") (pin "2") (pinfunction "2_2") (pintype "passive"))
      (node (ref "U15") (pin "4") (pinfunction "STBY_4") (pintype "passive"))
    )
    (net (code "26") (name "Net-(U15A-VBIAS)") (class "Default")
      (node (ref "C1309") (pin "1") (pinfunction "1_1") (pintype "passive"))
      (node (ref "U15") (pin "43") (pinfunction "VBIAS_43") (pintype "passive"))
    )
    (net (code "27") (name "Net-(U15A-VDIG)") (class "Default")
      (node (ref "C1306") (pin "1") (pinfunction "1_1") (pintype "passive"))
      (node (ref "U15") (pin "51") (pinfunction "VDIG_51") (pintype "passive"))
    )
    (net (code "28") (name "Net-(U15B-VLDOIN1)") (class "Default")
      (node (ref "C1265") (pin "1") (pinfunction "1_1") (pintype "passive"))
      (node (ref "C1266") (pin "1") (pinfunction "1_1") (pintype "passive"))
      (node (ref "C1267") (pin "1") (pinfunction "1_1") (pintype "passive"))
      (node (ref "U15") (pin "17") (pinfunction "VLDOIN1_17") (pintype "passive"))
      (node (ref "U15") (pin "27") (pinfunction "VLDOIN23_27") (pintype "passive"))
      (node (ref "U15") (pin "40") (pinfunction "VLDOIN45_40") (pintype "passive"))
    )
    (net (code "29") (name "PWR_X1VDD") (class "Default")
      (node (ref "C1268") (pin "2") (pinfunction "2_2") (pintype "passive"))
      (node (ref "U15") (pin "18") (pinfunction "LDO1_18") (pintype "passive"))
    )
    (net (code "30") (name "unconnected-(U15C-DNC1-Pad2)") (class "Default")
      (node (ref "U15") (pin "2") (pinfunction "DNC1_2") (pintype "passive+no_connect"))
    )
    (net (code "31") (name "unconnected-(U15C-DNC2-Pad6)") (class "Default")
      (node (ref "U15") (pin "6") (pinfunction "DNC2_6") (pintype "passive+no_connect"))
    )
    (net (code "32") (name "unconnected-(U15C-DNC3-Pad16)") (class "Default")
      (node (ref "U15") (pin "16") (pinfunction "DNC3_16") (pintype "passive+no_connect"))
    )
    (net (code "33") (name "unconnected-(U15C-DNC4-Pad33)") (class "Default")
      (node (ref "U15") (pin "33") (pinfunction "DNC4_33") (pintype "passive+no_connect"))
    )
    (net (code "34") (name "unconnected-(U15C-DNC5-Pad42)") (class "Default")
      (node (ref "U15") (pin "42") (pinfunction "DNC5_42") (pintype "passive+no_connect"))
    )
    (net (code "35") (name "unconnected-(U15C-DNC6-Pad44)") (class "Default")
      (node (ref "U15") (pin "44") (pinfunction "DNC6_44") (pintype "passive+no_connect"))
    )
    (net (code "36") (name "unconnected-(U15C-DNC7-Pad45)") (class "Default")
      (node (ref "U15") (pin "45") (pinfunction "DNC7_45") (pintype "passive+no_connect"))
    )
    (net (code "37") (name "unconnected-(U15C-DNC8-Pad46)") (class "Default")
      (node (ref "U15") (pin "46") (pinfunction "DNC8_46") (pintype "passive+no_connect"))
    )
  )
)
